# Smart-Home.net
KiCad netlist of a schematic drawn in EasyEDA
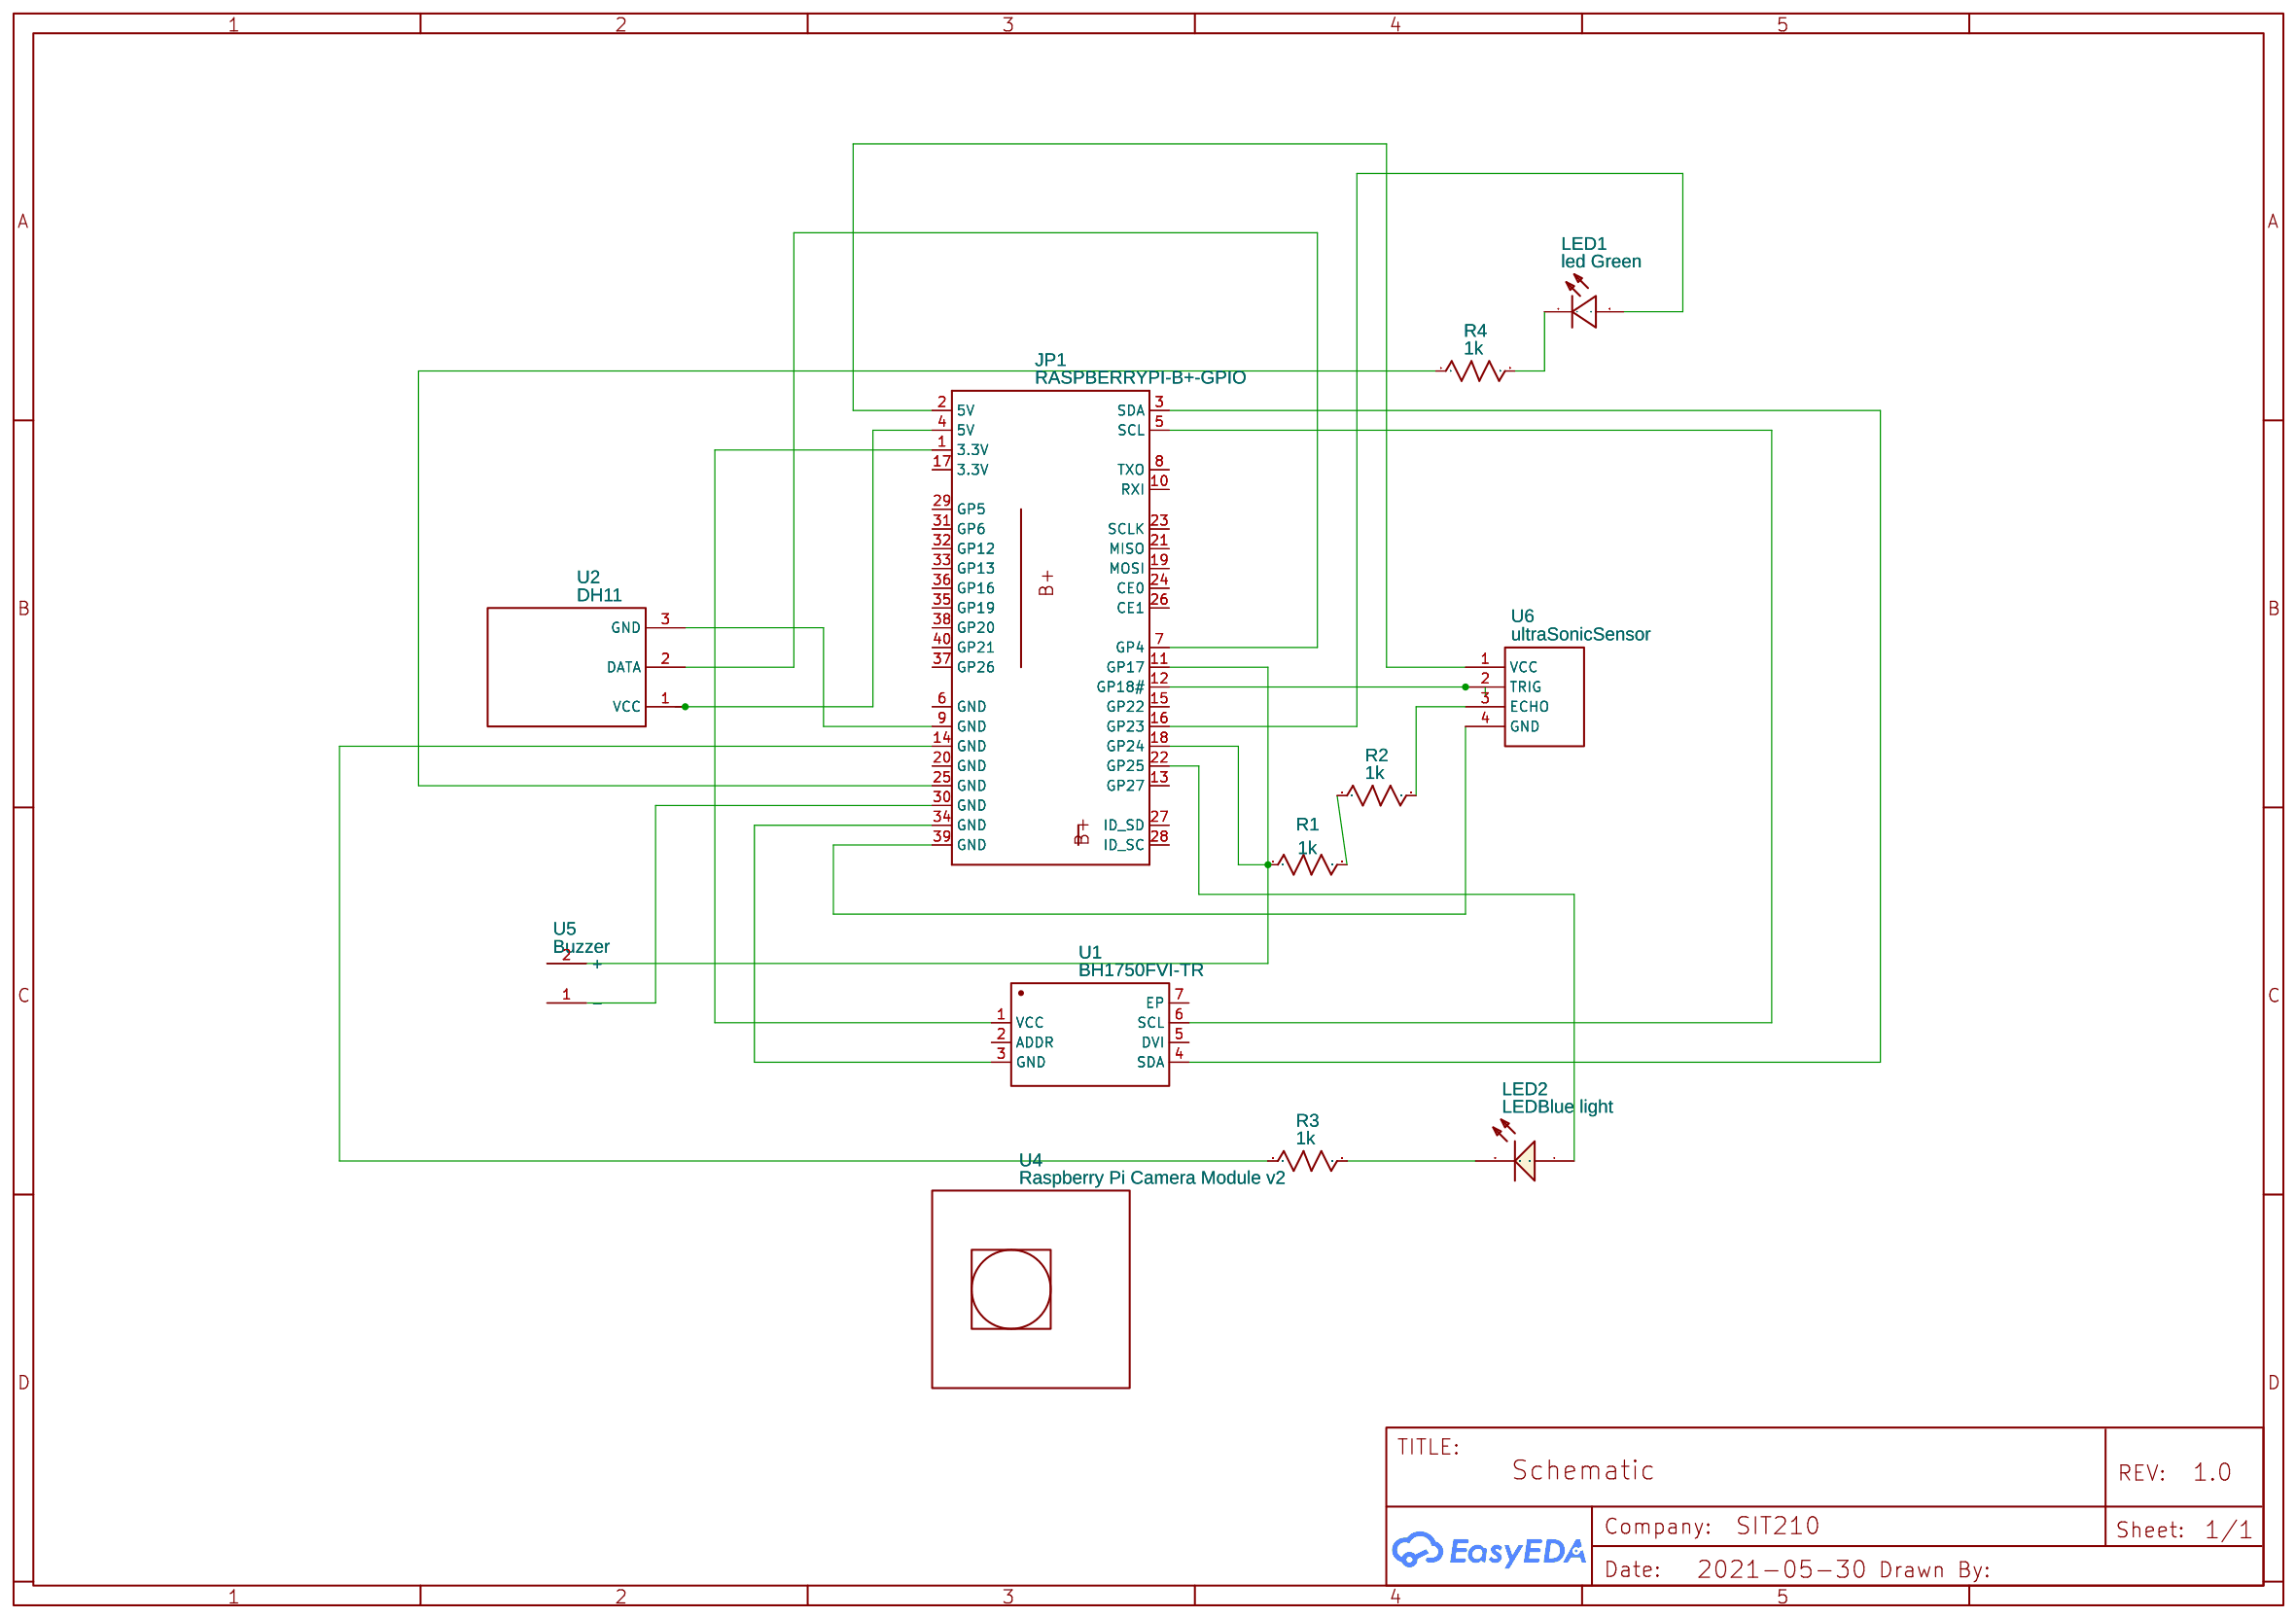
[diagram p0: schematic sheet]

(export (version "E")
  (design (tool "Eeschema 10.0.6"))
  (components
    (comp (ref "JP1") (value "RASPBERRYPI-B+-GPIO") (libsource (lib "") (part "RASPBERRYPI-B+-GPIO")))
    (comp (ref "LED1")
      (value "led Green")
      (fields (field (name "BOM_Supplier Part") "C14641"))
      (libsource (lib "") (part "led Green"))
    )
    (comp (ref "LED2")
      (value "LEDBlue light")
      (fields (field (name "BOM_Supplier Part") "C69273"))
      (libsource (lib "") (part "LEDBlue light"))
    )
    (comp (ref "R1") (value "1k") (libsource (lib "") (part "R_0603_US")))
    (comp (ref "R2") (value "1k") (libsource (lib "") (part "R_0603_US")))
    (comp (ref "R3") (value "1k") (libsource (lib "") (part "R_0603_US")))
    (comp (ref "R4") (value "1k") (libsource (lib "") (part "R_0603_US")))
    (comp (ref "U1")
      (value "BH1750FVI-TR")
      (fields (field (name "BOM_Supplier Part") "C78960"))
      (libsource (lib "") (part "BH1750FVI-TR"))
    )
    (comp (ref "U2")
      (value "DH11")
      (fields (field (name "BOM_Manufacturer Part") "New SchematicLib"))
      (libsource (lib "") (part "DH11"))
    )
    (comp (ref "U4")
      (value "Raspberry Pi Camera Module v2")
      (libsource (lib "") (part "Raspberry Pi Camera Module v2"))
    )
    (comp (ref "U5") (value "Buzzer") (libsource (lib "") (part "Buzzer")))
    (comp (ref "U6") (value "ultraSonicSensor") (libsource (lib "") (part "ultraSonicSensor")))
  )
  (nets
    (net (code "1") (name "Net-(JP1-GND-Pad14)") (class "Default")
      (node (ref "JP1") (pin "14") (pinfunction "GND_14") (pintype "passive"))
      (node (ref "R3") (pin "1") (pinfunction "1_1") (pintype "unspecified"))
    )
    (net (code "2") (name "Net-(JP1-GND-Pad25)") (class "Default")
      (node (ref "JP1") (pin "25") (pinfunction "GND_25") (pintype "passive"))
      (node (ref "R4") (pin "1") (pinfunction "1_1") (pintype "unspecified"))
    )
    (net (code "3") (name "Net-(JP1-GP4)") (class "Default")
      (node (ref "JP1") (pin "7") (pinfunction "GP4_7") (pintype "unspecified"))
      (node (ref "U2") (pin "2") (pinfunction "DATA_2") (pintype "unspecified"))
    )
    (net (code "4") (name "Net-(JP1-GP17)") (class "Default")
      (node (ref "JP1") (pin "11") (pinfunction "GP17_11") (pintype "unspecified"))
      (node (ref "JP1") (pin "18") (pinfunction "GP24_18") (pintype "unspecified"))
      (node (ref "R1") (pin "1") (pinfunction "1_1") (pintype "unspecified"))
      (node (ref "U5") (pin "2") (pinfunction "+_2") (pintype "unspecified"))
    )
    (net (code "5") (name "Net-(JP1-GP18#)") (class "Default")
      (node (ref "JP1") (pin "12") (pinfunction "GP18#_12") (pintype "unspecified"))
      (node (ref "U6") (pin "2") (pinfunction "TRIG_2") (pintype "unspecified"))
    )
    (net (code "6") (name "Net-(JP1-GP23)") (class "Default")
      (node (ref "JP1") (pin "16") (pinfunction "GP23_16") (pintype "unspecified"))
      (node (ref "LED1") (pin "2") (pinfunction "+_2") (pintype "unspecified"))
    )
    (net (code "7") (name "Net-(JP1-GP25)") (class "Default")
      (node (ref "JP1") (pin "22") (pinfunction "GP25_22") (pintype "unspecified"))
      (node (ref "LED2") (pin "1") (pinfunction "1_1") (pintype "input"))
    )
    (net (code "8") (name "Net-(JP1-SCL)") (class "Default")
      (node (ref "JP1") (pin "5") (pinfunction "SCL_5") (pintype "unspecified"))
      (node (ref "U1") (pin "6") (pinfunction "SCL_6") (pintype "unspecified"))
    )
    (net (code "9") (name "Net-(JP1-SDA)") (class "Default")
      (node (ref "JP1") (pin "3") (pinfunction "SDA_3") (pintype "unspecified"))
      (node (ref "U1") (pin "4") (pinfunction "SDA_4") (pintype "unspecified"))
    )
    (net (code "10") (name "Net-(LED1--)") (class "Default")
      (node (ref "LED1") (pin "1") (pinfunction "-_1") (pintype "unspecified"))
      (node (ref "R4") (pin "2") (pinfunction "2_2") (pintype "unspecified"))
    )
    (net (code "11") (name "Net-(LED2-Pad2)") (class "Default")
      (node (ref "LED2") (pin "2") (pinfunction "2_2") (pintype "input"))
      (node (ref "R3") (pin "2") (pinfunction "2_2") (pintype "unspecified"))
    )
    (net (code "12") (name "Net-(R1-Pad2)") (class "Default")
      (node (ref "R1") (pin "2") (pinfunction "2_2") (pintype "unspecified"))
      (node (ref "R2") (pin "1") (pinfunction "1_1") (pintype "unspecified"))
    )
    (net (code "13") (name "Net-(U1-GND)") (class "Default")
      (node (ref "JP1") (pin "34") (pinfunction "GND_34") (pintype "passive"))
      (node (ref "U1") (pin "3") (pinfunction "GND_3") (pintype "unspecified"))
    )
    (net (code "14") (name "Net-(U1-VCC)") (class "Default")
      (node (ref "JP1") (pin "1") (pinfunction "3.3V_1") (pintype "passive"))
      (node (ref "U1") (pin "1") (pinfunction "VCC_1") (pintype "unspecified"))
    )
    (net (code "15") (name "Net-(U2-GND)") (class "Default")
      (node (ref "JP1") (pin "9") (pinfunction "GND_9") (pintype "passive"))
      (node (ref "U2") (pin "3") (pinfunction "GND_3") (pintype "unspecified"))
    )
    (net (code "16") (name "Net-(U2-VCC)") (class "Default")
      (node (ref "JP1") (pin "4") (pinfunction "5V_4") (pintype "passive"))
      (node (ref "U2") (pin "1") (pinfunction "VCC_1") (pintype "unspecified"))
    )
    (net (code "17") (name "Net-(U5--)") (class "Default")
      (node (ref "JP1") (pin "30") (pinfunction "GND_30") (pintype "passive"))
      (node (ref "U5") (pin "1") (pinfunction "-_1") (pintype "unspecified"))
    )
    (net (code "18") (name "Net-(U6-ECHO)") (class "Default")
      (node (ref "R2") (pin "2") (pinfunction "2_2") (pintype "unspecified"))
      (node (ref "U6") (pin "3") (pinfunction "ECHO_3") (pintype "unspecified"))
    )
    (net (code "19") (name "Net-(U6-GND)") (class "Default")
      (node (ref "JP1") (pin "39") (pinfunction "GND_39") (pintype "passive"))
      (node (ref "U6") (pin "4") (pinfunction "GND_4") (pintype "unspecified"))
    )
    (net (code "20") (name "Net-(U6-VCC)") (class "Default")
      (node (ref "JP1") (pin "2") (pinfunction "5V_2") (pintype "passive"))
      (node (ref "U6") (pin "1") (pinfunction "VCC_1") (pintype "unspecified"))
    )
    (net (code "21") (name "unconnected-(JP1-3.3V-Pad17)") (class "Default")
      (node (ref "JP1") (pin "17") (pinfunction "3.3V_17") (pintype "passive"))
    )
    (net (code "22") (name "unconnected-(JP1-CE0-Pad24)") (class "Default")
      (node (ref "JP1") (pin "24") (pinfunction "CE0_24") (pintype "output"))
    )
    (net (code "23") (name "unconnected-(JP1-CE1-Pad26)") (class "Default")
      (node (ref "JP1") (pin "26") (pinfunction "CE1_26") (pintype "output"))
    )
    (net (code "24") (name "unconnected-(JP1-GND-Pad6)") (class "Default")
      (node (ref "JP1") (pin "6") (pinfunction "GND_6") (pintype "passive"))
    )
    (net (code "25") (name "unconnected-(JP1-GND-Pad20)") (class "Default")
      (node (ref "JP1") (pin "20") (pinfunction "GND_20") (pintype "passive"))
    )
    (net (code "26") (name "unconnected-(JP1-GP5-Pad29)") (class "Default")
      (node (ref "JP1") (pin "29") (pinfunction "GP5_29") (pintype "unspecified"))
    )
    (net (code "27") (name "unconnected-(JP1-GP6-Pad31)") (class "Default")
      (node (ref "JP1") (pin "31") (pinfunction "GP6_31") (pintype "unspecified"))
    )
    (net (code "28") (name "unconnected-(JP1-GP12-Pad32)") (class "Default")
      (node (ref "JP1") (pin "32") (pinfunction "GP12_32") (pintype "unspecified"))
    )
    (net (code "29") (name "unconnected-(JP1-GP13-Pad33)") (class "Default")
      (node (ref "JP1") (pin "33") (pinfunction "GP13_33") (pintype "unspecified"))
    )
    (net (code "30") (name "unconnected-(JP1-GP16-Pad36)") (class "Default")
      (node (ref "JP1") (pin "36") (pinfunction "GP16_36") (pintype "unspecified"))
    )
    (net (code "31") (name "unconnected-(JP1-GP19-Pad35)") (class "Default")
      (node (ref "JP1") (pin "35") (pinfunction "GP19_35") (pintype "unspecified"))
    )
    (net (code "32") (name "unconnected-(JP1-GP20-Pad38)") (class "Default")
      (node (ref "JP1") (pin "38") (pinfunction "GP20_38") (pintype "unspecified"))
    )
    (net (code "33") (name "unconnected-(JP1-GP21-Pad40)") (class "Default")
      (node (ref "JP1") (pin "40") (pinfunction "GP21_40") (pintype "unspecified"))
    )
    (net (code "34") (name "unconnected-(JP1-GP22-Pad15)") (class "Default")
      (node (ref "JP1") (pin "15") (pinfunction "GP22_15") (pintype "unspecified"))
    )
    (net (code "35") (name "unconnected-(JP1-GP26-Pad37)") (class "Default")
      (node (ref "JP1") (pin "37") (pinfunction "GP26_37") (pintype "unspecified"))
    )
    (net (code "36") (name "unconnected-(JP1-GP27-Pad13)") (class "Default")
      (node (ref "JP1") (pin "13") (pinfunction "GP27_13") (pintype "unspecified"))
    )
    (net (code "37") (name "unconnected-(JP1-ID_SC-Pad28)") (class "Default")
      (node (ref "JP1") (pin "28") (pinfunction "ID_SC_28") (pintype "unspecified"))
    )
    (net (code "38") (name "unconnected-(JP1-ID_SD-Pad27)") (class "Default")
      (node (ref "JP1") (pin "27") (pinfunction "ID_SD_27") (pintype "unspecified"))
    )
    (net (code "39") (name "unconnected-(JP1-MISO-Pad21)") (class "Default")
      (node (ref "JP1") (pin "21") (pinfunction "MISO_21") (pintype "input"))
    )
    (net (code "40") (name "unconnected-(JP1-MOSI-Pad19)") (class "Default")
      (node (ref "JP1") (pin "19") (pinfunction "MOSI_19") (pintype "output"))
    )
    (net (code "41") (name "unconnected-(JP1-RXI-Pad10)") (class "Default")
      (node (ref "JP1") (pin "10") (pinfunction "RXI_10") (pintype "input"))
    )
    (net (code "42") (name "unconnected-(JP1-SCLK-Pad23)") (class "Default")
      (node (ref "JP1") (pin "23") (pinfunction "SCLK_23") (pintype "output"))
    )
    (net (code "43") (name "unconnected-(JP1-TXO-Pad8)") (class "Default")
      (node (ref "JP1") (pin "8") (pinfunction "TXO_8") (pintype "output"))
    )
    (net (code "44") (name "unconnected-(U1-ADDR-Pad2)") (class "Default")
      (node (ref "U1") (pin "2") (pinfunction "ADDR_2") (pintype "unspecified"))
    )
    (net (code "45") (name "unconnected-(U1-DVI-Pad5)") (class "Default")
      (node (ref "U1") (pin "5") (pinfunction "DVI_5") (pintype "unspecified"))
    )
    (net (code "46") (name "unconnected-(U1-EP-Pad7)") (class "Default")
      (node (ref "U1") (pin "7") (pinfunction "EP_7") (pintype "unspecified"))
    )
  )
)
